# selfbus_dap_debugger.net
KiCad netlist of a schematic drawn in EAGLE
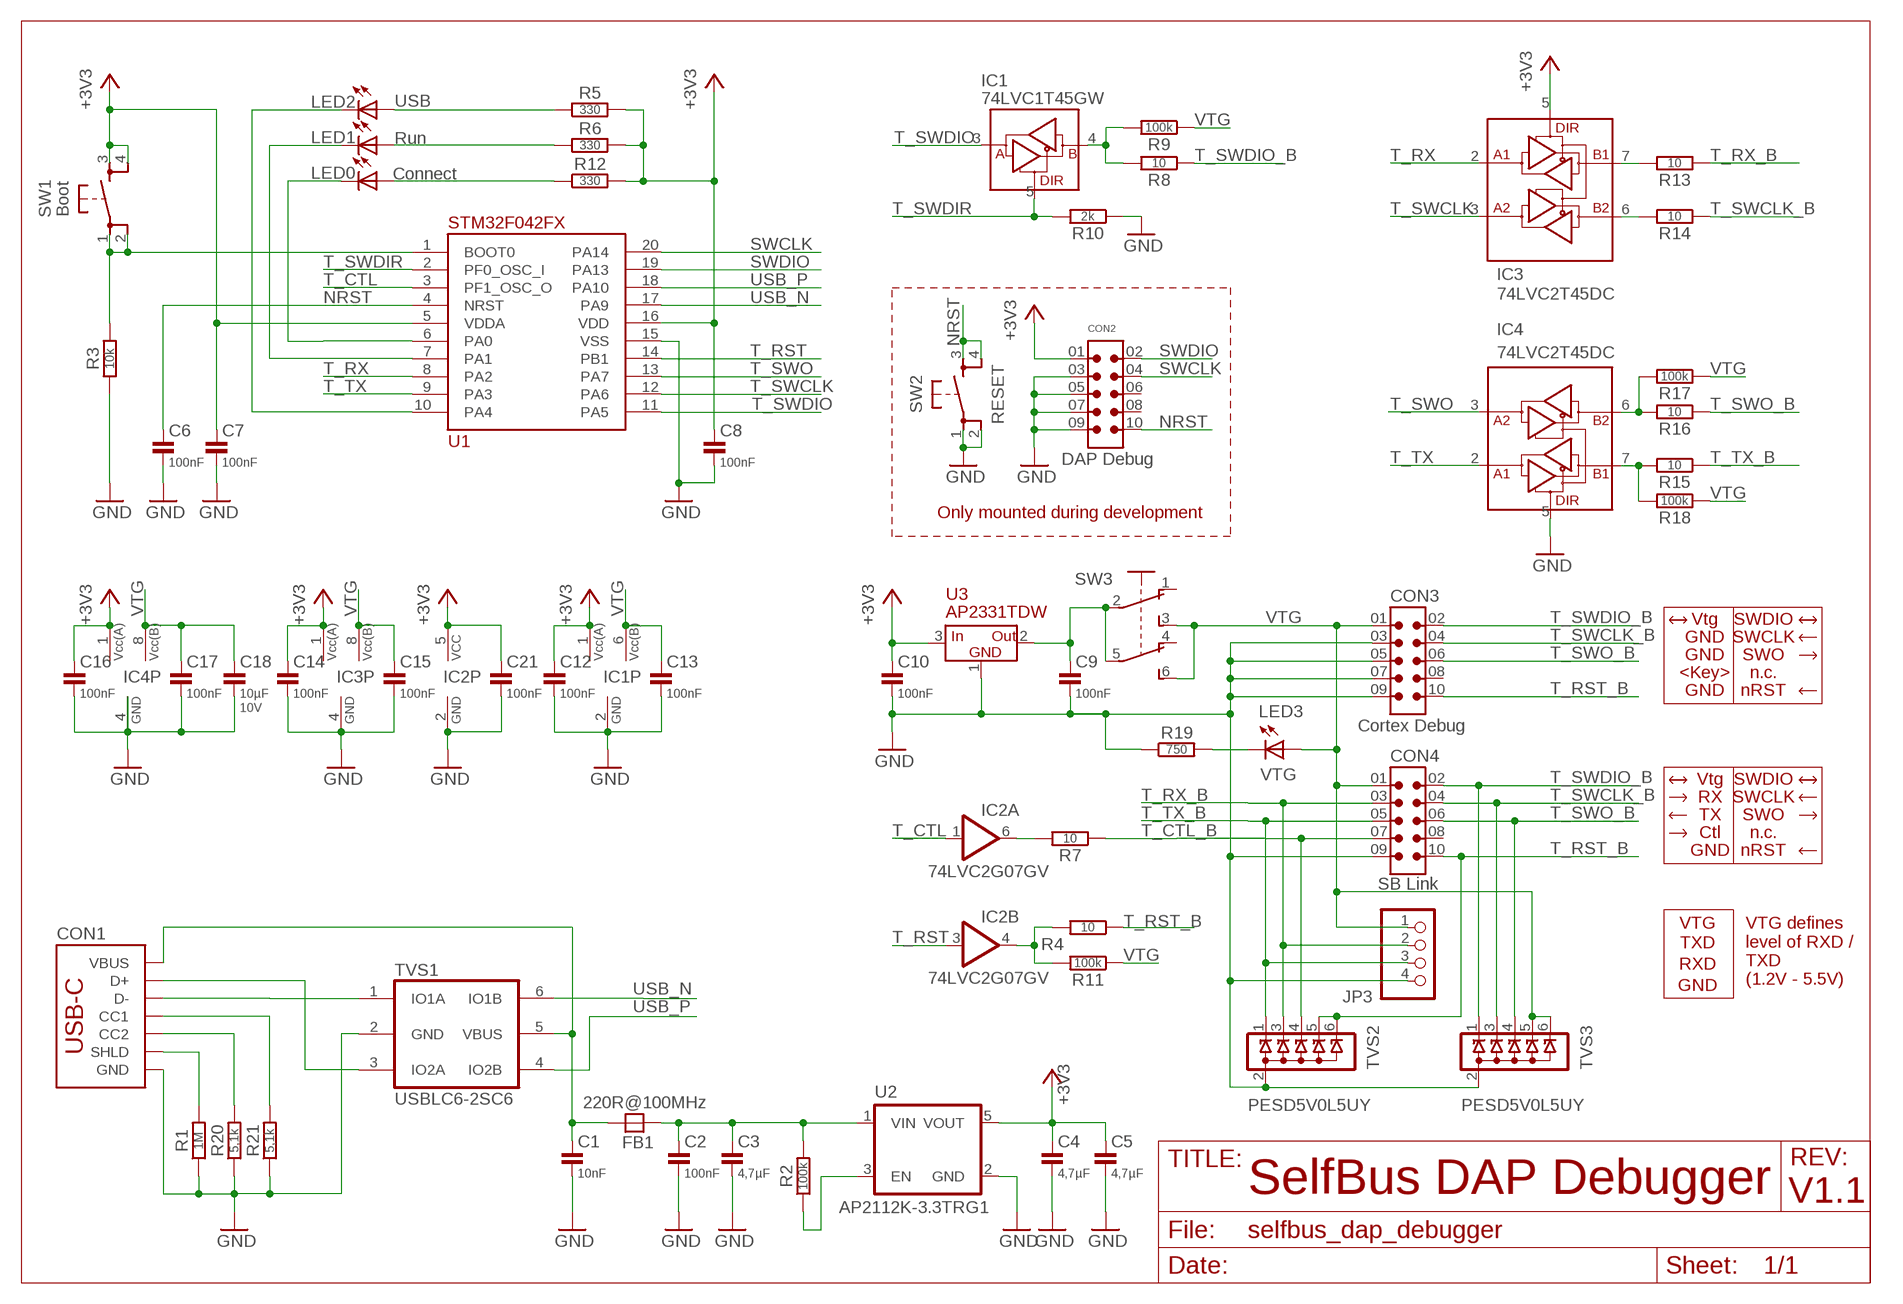
[diagram p0: schematic, sheet 1]

(export (version "E")
  (design (tool "Eeschema 10.0.6"))
  (components
    (comp (ref "C1")
      (value "10nF")
      (footprint "eagle-import:C0805")
      (libsource (lib "eagle-import") (part "C-EUC0805"))
    )
    (comp (ref "C2")
      (value "100nF")
      (footprint "eagle-import:C0805")
      (libsource (lib "eagle-import") (part "C-EUC0805"))
    )
    (comp (ref "C3")
      (value "4,7µF")
      (footprint "eagle-import:C0805")
      (libsource (lib "eagle-import") (part "C-EUC0805"))
    )
    (comp (ref "C4")
      (value "4,7µF")
      (footprint "eagle-import:C0805")
      (libsource (lib "eagle-import") (part "C-EUC0805"))
    )
    (comp (ref "C5")
      (value "4,7µF")
      (footprint "eagle-import:C0805")
      (libsource (lib "eagle-import") (part "C-EUC0805"))
    )
    (comp (ref "C6")
      (value "100nF")
      (footprint "eagle-import:C0805")
      (libsource (lib "eagle-import") (part "C-EUC0805"))
    )
    (comp (ref "C7")
      (value "100nF")
      (footprint "eagle-import:C0805")
      (libsource (lib "eagle-import") (part "C-EUC0805"))
    )
    (comp (ref "C8")
      (value "100nF")
      (footprint "eagle-import:C0805")
      (libsource (lib "eagle-import") (part "C-EUC0805"))
    )
    (comp (ref "C9")
      (value "100nF")
      (footprint "eagle-import:C0805")
      (libsource (lib "eagle-import") (part "C-EUC0805"))
    )
    (comp (ref "C10")
      (value "100nF")
      (footprint "eagle-import:C0805")
      (libsource (lib "eagle-import") (part "C-EUC0805"))
    )
    (comp (ref "C12")
      (value "100nF")
      (footprint "eagle-import:C0805")
      (libsource (lib "eagle-import") (part "C-EUC0805"))
    )
    (comp (ref "C13")
      (value "100nF")
      (footprint "eagle-import:C0805")
      (libsource (lib "eagle-import") (part "C-EUC0805"))
    )
    (comp (ref "C14")
      (value "100nF")
      (footprint "eagle-import:C0805")
      (libsource (lib "eagle-import") (part "C-EUC0805"))
    )
    (comp (ref "C15")
      (value "100nF")
      (footprint "eagle-import:C0805")
      (libsource (lib "eagle-import") (part "C-EUC0805"))
    )
    (comp (ref "C16")
      (value "100nF")
      (footprint "eagle-import:C0805")
      (libsource (lib "eagle-import") (part "C-EUC0805"))
    )
    (comp (ref "C17")
      (value "100nF")
      (footprint "eagle-import:C0805")
      (libsource (lib "eagle-import") (part "C-EUC0805"))
    )
    (comp (ref "C18")
      (value "10µF")
      (footprint "eagle-import:C0805")
      (fields (field (name "VOLTAGE") "10V"))
      (libsource (lib "eagle-import") (part "C-EUC0805"))
    )
    (comp (ref "C21")
      (value "100nF")
      (footprint "eagle-import:C0805")
      (libsource (lib "eagle-import") (part "C-EUC0805"))
    )
    (comp (ref "CON1")
      (value "XKB U262-161N-4BVC11")
      (footprint "eagle-import:USB-C-16P-2LAYER-PADS")
      (libsource (lib "eagle-import") (part "USB_C_2-LAYER_PADS"))
    )
    (comp (ref "CON2")
      (value "SHF-105-01-X-D-TH")
      (footprint "eagle-import:SAMTEC_SHF-105-01-X-D-TH")
      (libsource (lib "eagle-import") (part "SHF-105-01-X-D-TH"))
    )
    (comp (ref "CON3")
      (value "SHF-105-01-X-D-TH")
      (footprint "eagle-import:SAMTEC_SHF-105-01-X-D-TH")
      (libsource (lib "eagle-import") (part "SHF-105-01-X-D-TH"))
    )
    (comp (ref "CON4")
      (value "SAMTEC-LTMM-105-02-T-D")
      (footprint "eagle-import:SAMTEC-LTMM-105-02-T-D")
      (libsource (lib "eagle-import") (part "SAMTEC-LTMM-105-02-T-D"))
    )
    (comp (ref "FB1")
      (value "220R@100MHz")
      (footprint "eagle-import:FB0805")
      (fields (field (name "PART#") "MPZ2012S221ATD25"))
      (libsource (lib "eagle-import") (part "FB"))
    )
    (comp (ref "IC1")
      (value "74LVC1T45GW")
      (footprint "eagle-import:SOT363")
      (fields
        (field (name "LCSC#") "C478004")
        (field (name "LCSC#2") "C548484")
        (field (name "LCSC#3") "C9382")
        (field (name "MOUSER#") "771-74LVC1T45GW125")
        (field (name "MOUSER#2") "771-74LVC1T45GWQ100H")
        (field (name "MOUSER#3") "595-74LVC1T45QDCKRQ1")
        (field (name "PART#") "74LVC1T45GW,125")
        (field (name "PART#2") "74LVC1T45GW-Q100H")
        (field (name "PART#3") "SN74LVC1T45DCKR")
        (field (name "PART_MFR") "NXP")
        (field (name "PART_MFR2") "NXP")
        (field (name "PART_MFR3") "TI")
      )
      (libsource (lib "eagle-import") (part "741T45GWLVC"))
    )
    (comp (ref "IC2")
      (value "74LVC2G07GV")
      (footprint "eagle-import:SOT23-6")
      (fields
        (field (name "LCSC#") "C548568")
        (field (name "MOUSER#") "771-LVC2G07GV125")
        (field (name "PART#") "74LVC2G07GV,125")
        (field (name "PART_MFR") "NXP")
      )
      (libsource (lib "eagle-import") (part "742G07GVLVC"))
    )
    (comp (ref "IC3")
      (value "74LVC2T45DC")
      (footprint "eagle-import:VSSOP8(0.5)")
      (fields
        (field (name "LCSC#") "C15741")
        (field (name "LCSC#2") "C139524")
        (field (name "MOUSER#") "595-SN74LVC2T45DCUT")
        (field (name "MOUSER#2") "771-74LVCH2T45DC125")
        (field (name "PART#") "SN74LVC2T45DCU")
        (field (name "PART#2") "74LVCH2T45DC,125")
        (field (name "PART_MFR") "TI")
        (field (name "PART_MFR2") "NXP")
      )
      (libsource (lib "eagle-import") (part "742T45DCLVC"))
    )
    (comp (ref "IC4")
      (value "74LVC2T45DC")
      (footprint "eagle-import:VSSOP8(0.5)")
      (libsource (lib "eagle-import") (part "742T45DCLVC"))
    )
    (comp (ref "JP3")
      (value "PINHD-1X4")
      (footprint "eagle-import:1X04")
      (libsource (lib "eagle-import") (part "PINHD-1X4"))
    )
    (comp (ref "LED0")
      (value "Connect")
      (footprint "eagle-import:LED_3MM_GREEN")
      (libsource (lib "eagle-import") (part "LED_3MM(T1)_GREEN"))
    )
    (comp (ref "LED1")
      (value "Run")
      (footprint "eagle-import:LED_3MM_YELLOW")
      (libsource (lib "eagle-import") (part "LED_3MM(T1)_YELLOW"))
    )
    (comp (ref "LED2")
      (value "USB")
      (footprint "eagle-import:LED_3MM_GREEN")
      (libsource (lib "eagle-import") (part "LED_3MM(T1)_GREEN"))
    )
    (comp (ref "LED3")
      (value "VTG")
      (footprint "eagle-import:LED_3MM_RED")
      (libsource (lib "eagle-import") (part "LED_3MM(T1)_RED"))
    )
    (comp (ref "R1")
      (value "1M")
      (footprint "eagle-import:R0805")
      (libsource (lib "eagle-import") (part "R-EU_R0805"))
    )
    (comp (ref "R2")
      (value "100k")
      (footprint "eagle-import:R0805")
      (libsource (lib "eagle-import") (part "R-EU_R0805"))
    )
    (comp (ref "R3")
      (value "10k")
      (footprint "eagle-import:R0805")
      (libsource (lib "eagle-import") (part "R-EU_R0805"))
    )
    (comp (ref "R4")
      (value "10")
      (footprint "eagle-import:R0805")
      (libsource (lib "eagle-import") (part "R-EU_R0805"))
    )
    (comp (ref "R5")
      (value "330")
      (footprint "eagle-import:R0805")
      (libsource (lib "eagle-import") (part "R-EU_R0805"))
    )
    (comp (ref "R6")
      (value "330")
      (footprint "eagle-import:R0805")
      (libsource (lib "eagle-import") (part "R-EU_R0805"))
    )
    (comp (ref "R7")
      (value "10")
      (footprint "eagle-import:R0805")
      (libsource (lib "eagle-import") (part "R-EU_R0805"))
    )
    (comp (ref "R8")
      (value "10")
      (footprint "eagle-import:R0805")
      (libsource (lib "eagle-import") (part "R-EU_R0805"))
    )
    (comp (ref "R9")
      (value "100k")
      (footprint "eagle-import:R0805")
      (libsource (lib "eagle-import") (part "R-EU_R0805"))
    )
    (comp (ref "R10")
      (value "2k")
      (footprint "eagle-import:R0805")
      (libsource (lib "eagle-import") (part "R-EU_R0805"))
    )
    (comp (ref "R11")
      (value "100k")
      (footprint "eagle-import:R0805")
      (libsource (lib "eagle-import") (part "R-EU_R0805"))
    )
    (comp (ref "R12")
      (value "330")
      (footprint "eagle-import:R0805")
      (libsource (lib "eagle-import") (part "R-EU_R0805"))
    )
    (comp (ref "R13")
      (value "10")
      (footprint "eagle-import:R0805")
      (libsource (lib "eagle-import") (part "R-EU_R0805"))
    )
    (comp (ref "R14")
      (value "10")
      (footprint "eagle-import:R0805")
      (libsource (lib "eagle-import") (part "R-EU_R0805"))
    )
    (comp (ref "R15")
      (value "10")
      (footprint "eagle-import:R0805")
      (libsource (lib "eagle-import") (part "R-EU_R0805"))
    )
    (comp (ref "R16")
      (value "10")
      (footprint "eagle-import:R0805")
      (libsource (lib "eagle-import") (part "R-EU_R0805"))
    )
    (comp (ref "R17")
      (value "100k")
      (footprint "eagle-import:R0805")
      (libsource (lib "eagle-import") (part "R-EU_R0805"))
    )
    (comp (ref "R18")
      (value "100k")
      (footprint "eagle-import:R0805")
      (libsource (lib "eagle-import") (part "R-EU_R0805"))
    )
    (comp (ref "R19")
      (value "750")
      (footprint "eagle-import:R0805")
      (libsource (lib "eagle-import") (part "R-EU_R0805"))
    )
    (comp (ref "R20")
      (value "5,1k")
      (footprint "eagle-import:R0805")
      (libsource (lib "eagle-import") (part "R-EU_R0805"))
    )
    (comp (ref "R21")
      (value "5,1k")
      (footprint "eagle-import:R0805")
      (libsource (lib "eagle-import") (part "R-EU_R0805"))
    )
    (comp (ref "SW1")
      (value "BOOT")
      (footprint "eagle-import:TACT_SWITCH_6X6_SNAP-IN_17")
      (fields (field (name "PART#") "SKHHDHA010"))
      (libsource (lib "eagle-import") (part "ALPS_SKHHDHA010"))
    )
    (comp (ref "SW2")
      (value "RESET")
      (footprint "eagle-import:TACT_SWITCH_6X6_SNAP-IN_17")
      (fields (field (name "PART#") "SKHHDHA010"))
      (libsource (lib "eagle-import") (part "ALPS_SKHHDHA010"))
    )
    (comp (ref "SW3")
      (value "XKB7070-Z")
      (footprint "eagle-import:XKB7070")
      (libsource (lib "eagle-import") (part "XKB7070-Z"))
    )
    (comp (ref "TVS1")
      (value "USBLC6-2SC6")
      (footprint "eagle-import:SOT-23-6L")
      (libsource (lib "eagle-import") (part "USBLC6-2SC6"))
    )
    (comp (ref "TVS2")
      (value "PESD5V0L5UY")
      (footprint "eagle-import:SOT363")
      (libsource (lib "eagle-import") (part "PESD5V0L5UY"))
    )
    (comp (ref "TVS3")
      (value "PESD5V0L5UY")
      (footprint "eagle-import:SOT363")
      (libsource (lib "eagle-import") (part "PESD5V0L5UY"))
    )
    (comp (ref "U1")
      (value "STM32F042FX")
      (footprint "eagle-import:TSSOP20")
      (fields (field (name "PART#") "STM32F042F4P6"))
      (libsource (lib "eagle-import") (part "STM32F042FX"))
    )
    (comp (ref "U2")
      (value "AP2112K-3.3TRG1")
      (footprint "eagle-import:SOT23-5")
      (libsource (lib "eagle-import") (part "AP2112K-3.3TRG1"))
    )
    (comp (ref "U3")
      (value "AP2331TDW")
      (footprint "eagle-import:SC59")
      (fields (field (name "PART#") "AP2331W-7"))
      (libsource (lib "eagle-import") (part "AP2331TDW"))
    )
  )
  (nets
    (net (code "1") (name "+3V3") (class "Default")
      (node (ref "C10") (pin "1") (pinfunction "1_1") (pintype "passive"))
      (node (ref "C12") (pin "1") (pinfunction "1_1") (pintype "passive"))
      (node (ref "C14") (pin "1") (pinfunction "1_1") (pintype "passive"))
      (node (ref "C16") (pin "1") (pinfunction "1_1") (pintype "passive"))
      (node (ref "C21") (pin "1") (pinfunction "1_1") (pintype "passive"))
      (node (ref "C4") (pin "1") (pinfunction "1_1") (pintype "passive"))
      (node (ref "C5") (pin "1") (pinfunction "1_1") (pintype "passive"))
      (node (ref "C7") (pin "1") (pinfunction "1_1") (pintype "passive"))
      (node (ref "C8") (pin "1") (pinfunction "1_1") (pintype "passive"))
      (node (ref "CON2") (pin "01") (pinfunction "1_01") (pintype "passive"))
      (node (ref "IC1") (pin "1") (pinfunction "VCC(A)_1") (pintype "power_in"))
      (node (ref "IC2") (pin "5") (pinfunction "VCC_5") (pintype "power_in"))
      (node (ref "IC3") (pin "1") (pinfunction "VCC(A)_1") (pintype "power_in"))
      (node (ref "IC3") (pin "5") (pinfunction "DIR_5") (pintype "input"))
      (node (ref "IC4") (pin "1") (pinfunction "VCC(A)_1") (pintype "power_in"))
      (node (ref "R12") (pin "2") (pinfunction "2_2") (pintype "passive"))
      (node (ref "R5") (pin "2") (pinfunction "2_2") (pintype "passive"))
      (node (ref "R6") (pin "2") (pinfunction "2_2") (pintype "passive"))
      (node (ref "SW1") (pin "3") (pinfunction "3_3") (pintype "passive"))
      (node (ref "SW1") (pin "4") (pinfunction "4_4") (pintype "passive"))
      (node (ref "U1") (pin "16") (pinfunction "VDD_16") (pintype "power_in"))
      (node (ref "U1") (pin "5") (pinfunction "VDDA_5") (pintype "power_in"))
      (node (ref "U2") (pin "5") (pinfunction "VOUT_5") (pintype "passive"))
      (node (ref "U3") (pin "3") (pinfunction "IN_3") (pintype "bidirectional"))
    )
    (net (code "2") (name "/NRST") (class "Default")
      (node (ref "C6") (pin "1") (pinfunction "1_1") (pintype "passive"))
      (node (ref "CON2") (pin "10") (pinfunction "10_10") (pintype "passive"))
      (node (ref "SW2") (pin "3") (pinfunction "3_3") (pintype "passive"))
      (node (ref "SW2") (pin "4") (pinfunction "4_4") (pintype "passive"))
      (node (ref "U1") (pin "4") (pinfunction "NRST_4") (pintype "input"))
    )
    (net (code "3") (name "/SWCLK") (class "Default")
      (node (ref "CON2") (pin "04") (pinfunction "4_04") (pintype "passive"))
      (node (ref "U1") (pin "20") (pinfunction "PA14_20") (pintype "bidirectional"))
    )
    (net (code "4") (name "/SWDIO") (class "Default")
      (node (ref "CON2") (pin "02") (pinfunction "2_02") (pintype "passive"))
      (node (ref "U1") (pin "19") (pinfunction "PA13_19") (pintype "bidirectional"))
    )
    (net (code "5") (name "/T_CTL") (class "Default")
      (node (ref "IC2") (pin "1") (pinfunction "IN_1") (pintype "input"))
      (node (ref "U1") (pin "3") (pinfunction "PF1_OSC_O_3") (pintype "bidirectional"))
    )
    (net (code "6") (name "/T_CTL_B") (class "Default")
      (node (ref "CON4") (pin "07") (pinfunction "7_07") (pintype "passive"))
      (node (ref "R7") (pin "1") (pinfunction "1_1") (pintype "passive"))
      (node (ref "TVS2") (pin "4") (pinfunction "C3_4") (pintype "passive"))
    )
    (net (code "7") (name "/T_RST") (class "Default")
      (node (ref "IC2") (pin "3") (pinfunction "IN_3") (pintype "input"))
      (node (ref "U1") (pin "14") (pinfunction "PB1_14") (pintype "bidirectional"))
    )
    (net (code "8") (name "/T_RST_B") (class "Default")
      (node (ref "CON3") (pin "10") (pinfunction "10_10") (pintype "passive"))
      (node (ref "CON4") (pin "10") (pinfunction "10_10") (pintype "passive"))
      (node (ref "R4") (pin "1") (pinfunction "1_1") (pintype "passive"))
      (node (ref "TVS2") (pin "5") (pinfunction "C4_5") (pintype "passive"))
      (node (ref "TVS2") (pin "6") (pinfunction "C5_6") (pintype "passive"))
    )
    (net (code "9") (name "/T_RX") (class "Default")
      (node (ref "IC3") (pin "2") (pinfunction "A1_2") (pintype "bidirectional"))
      (node (ref "U1") (pin "8") (pinfunction "PA2_8") (pintype "bidirectional"))
    )
    (net (code "10") (name "/T_RX_B") (class "Default")
      (node (ref "CON4") (pin "03") (pinfunction "3_03") (pintype "passive"))
      (node (ref "JP3") (pin "2") (pinfunction "2_2") (pintype "passive"))
      (node (ref "R13") (pin "1") (pinfunction "1_1") (pintype "passive"))
      (node (ref "TVS2") (pin "3") (pinfunction "C2_3") (pintype "passive"))
    )
    (net (code "11") (name "/T_SWCLK") (class "Default")
      (node (ref "IC3") (pin "3") (pinfunction "A2_3") (pintype "bidirectional"))
      (node (ref "U1") (pin "12") (pinfunction "PA6_12") (pintype "bidirectional"))
    )
    (net (code "12") (name "/T_SWCLK_B") (class "Default")
      (node (ref "CON3") (pin "04") (pinfunction "4_04") (pintype "passive"))
      (node (ref "CON4") (pin "04") (pinfunction "4_04") (pintype "passive"))
      (node (ref "R14") (pin "1") (pinfunction "1_1") (pintype "passive"))
      (node (ref "TVS3") (pin "3") (pinfunction "C2_3") (pintype "passive"))
    )
    (net (code "13") (name "/T_SWDIO") (class "Default")
      (node (ref "IC1") (pin "3") (pinfunction "A_3") (pintype "bidirectional"))
      (node (ref "U1") (pin "11") (pinfunction "PA5_11") (pintype "bidirectional"))
    )
    (net (code "14") (name "/T_SWDIO_B") (class "Default")
      (node (ref "CON3") (pin "02") (pinfunction "2_02") (pintype "passive"))
      (node (ref "CON4") (pin "02") (pinfunction "2_02") (pintype "passive"))
      (node (ref "R8") (pin "1") (pinfunction "1_1") (pintype "passive"))
      (node (ref "TVS3") (pin "1") (pinfunction "C1_1") (pintype "passive"))
    )
    (net (code "15") (name "/T_SWDIR") (class "Default")
      (node (ref "IC1") (pin "5") (pinfunction "DIR_5") (pintype "input"))
      (node (ref "R10") (pin "2") (pinfunction "2_2") (pintype "passive"))
      (node (ref "U1") (pin "2") (pinfunction "PF0_OSC_I_2") (pintype "bidirectional"))
    )
    (net (code "16") (name "/T_SWO") (class "Default")
      (node (ref "IC4") (pin "3") (pinfunction "A2_3") (pintype "bidirectional"))
      (node (ref "U1") (pin "13") (pinfunction "PA7_13") (pintype "bidirectional"))
    )
    (net (code "17") (name "/T_SWO_B") (class "Default")
      (node (ref "CON3") (pin "06") (pinfunction "6_06") (pintype "passive"))
      (node (ref "CON4") (pin "06") (pinfunction "6_06") (pintype "passive"))
      (node (ref "R16") (pin "1") (pinfunction "1_1") (pintype "passive"))
      (node (ref "TVS3") (pin "4") (pinfunction "C3_4") (pintype "passive"))
    )
    (net (code "18") (name "/T_TX") (class "Default")
      (node (ref "IC4") (pin "2") (pinfunction "A1_2") (pintype "bidirectional"))
      (node (ref "U1") (pin "9") (pinfunction "PA3_9") (pintype "bidirectional"))
    )
    (net (code "19") (name "/T_TX_B") (class "Default")
      (node (ref "CON4") (pin "05") (pinfunction "5_05") (pintype "passive"))
      (node (ref "JP3") (pin "3") (pinfunction "3_3") (pintype "passive"))
      (node (ref "R15") (pin "1") (pinfunction "1_1") (pintype "passive"))
      (node (ref "TVS2") (pin "1") (pinfunction "C1_1") (pintype "passive"))
    )
    (net (code "20") (name "/USB_N") (class "Default")
      (node (ref "TVS1") (pin "6") (pinfunction "IO1B_6") (pintype "bidirectional"))
      (node (ref "U1") (pin "17") (pinfunction "PA9_17") (pintype "bidirectional"))
    )
    (net (code "21") (name "/USB_P") (class "Default")
      (node (ref "TVS1") (pin "4") (pinfunction "IO2B_4") (pintype "bidirectional"))
      (node (ref "U1") (pin "18") (pinfunction "PA10_18") (pintype "bidirectional"))
    )
    (net (code "22") (name "/VTG") (class "Default")
      (node (ref "C13") (pin "1") (pinfunction "1_1") (pintype "passive"))
      (node (ref "C15") (pin "1") (pinfunction "1_1") (pintype "passive"))
      (node (ref "C17") (pin "1") (pinfunction "1_1") (pintype "passive"))
      (node (ref "C18") (pin "1") (pinfunction "1_1") (pintype "passive"))
      (node (ref "CON3") (pin "01") (pinfunction "1_01") (pintype "passive"))
      (node (ref "CON4") (pin "01") (pinfunction "1_01") (pintype "passive"))
      (node (ref "IC1") (pin "6") (pinfunction "VCC(B)_6") (pintype "power_in"))
      (node (ref "IC3") (pin "8") (pinfunction "VCC(B)_8") (pintype "power_in"))
      (node (ref "IC4") (pin "8") (pinfunction "VCC(B)_8") (pintype "power_in"))
      (node (ref "JP3") (pin "1") (pinfunction "1_1") (pintype "passive"))
      (node (ref "LED3") (pin "A") (pinfunction "A_A") (pintype "passive"))
      (node (ref "R11") (pin "1") (pinfunction "1_1") (pintype "passive"))
      (node (ref "R17") (pin "1") (pinfunction "1_1") (pintype "passive"))
      (node (ref "R18") (pin "1") (pinfunction "1_1") (pintype "passive"))
      (node (ref "R9") (pin "1") (pinfunction "1_1") (pintype "passive"))
      (node (ref "SW3") (pin "3") (pinfunction "S_3") (pintype "passive"))
      (node (ref "SW3") (pin "6") (pinfunction "S_6") (pintype "passive"))
      (node (ref "TVS3") (pin "5") (pinfunction "C4_5") (pintype "passive"))
      (node (ref "TVS3") (pin "6") (pinfunction "C5_6") (pintype "passive"))
    )
    (net (code "23") (name "GND") (class "Default")
      (node (ref "C1") (pin "2") (pinfunction "2_2") (pintype "passive"))
      (node (ref "C10") (pin "2") (pinfunction "2_2") (pintype "passive"))
      (node (ref "C12") (pin "2") (pinfunction "2_2") (pintype "passive"))
      (node (ref "C13") (pin "2") (pinfunction "2_2") (pintype "passive"))
      (node (ref "C14") (pin "2") (pinfunction "2_2") (pintype "passive"))
      (node (ref "C15") (pin "2") (pinfunction "2_2") (pintype "passive"))
      (node (ref "C16") (pin "2") (pinfunction "2_2") (pintype "passive"))
      (node (ref "C17") (pin "2") (pinfunction "2_2") (pintype "passive"))
      (node (ref "C18") (pin "2") (pinfunction "2_2") (pintype "passive"))
      (node (ref "C2") (pin "2") (pinfunction "2_2") (pintype "passive"))
      (node (ref "C21") (pin "2") (pinfunction "2_2") (pintype "passive"))
      (node (ref "C3") (pin "2") (pinfunction "2_2") (pintype "passive"))
      (node (ref "C4") (pin "2") (pinfunction "2_2") (pintype "passive"))
      (node (ref "C5") (pin "2") (pinfunction "2_2") (pintype "passive"))
      (node (ref "C6") (pin "2") (pinfunction "2_2") (pintype "passive"))
      (node (ref "C7") (pin "2") (pinfunction "2_2") (pintype "passive"))
      (node (ref "C8") (pin "2") (pinfunction "2_2") (pintype "passive"))
      (node (ref "C9") (pin "2") (pinfunction "2_2") (pintype "passive"))
      (node (ref "CON1") (pin "GND") (pinfunction "GND_GND") (pintype "bidirectional"))
      (node (ref "CON1") (pin "GND2") (pinfunction "GND_GND2") (pintype "bidirectional"))
      (node (ref "CON2") (pin "03") (pinfunction "3_03") (pintype "passive"))
      (node (ref "CON2") (pin "05") (pinfunction "5_05") (pintype "passive"))
      (node (ref "CON2") (pin "07") (pinfunction "7_07") (pintype "passive"))
      (node (ref "CON2") (pin "09") (pinfunction "9_09") (pintype "passive"))
      (node (ref "CON3") (pin "03") (pinfunction "3_03") (pintype "passive"))
      (node (ref "CON3") (pin "05") (pinfunction "5_05") (pintype "passive"))
      (node (ref "CON3") (pin "07") (pinfunction "7_07") (pintype "passive"))
      (node (ref "CON3") (pin "09") (pinfunction "9_09") (pintype "passive"))
      (node (ref "CON4") (pin "09") (pinfunction "9_09") (pintype "passive"))
      (node (ref "IC1") (pin "2") (pinfunction "GND_2") (pintype "power_in"))
      (node (ref "IC2") (pin "2") (pinfunction "GND_2") (pintype "power_in"))
      (node (ref "IC3") (pin "4") (pinfunction "GND_4") (pintype "power_in"))
      (node (ref "IC4") (pin "4") (pinfunction "GND_4") (pintype "power_in"))
      (node (ref "IC4") (pin "5") (pinfunction "DIR_5") (pintype "input"))
      (node (ref "JP3") (pin "4") (pinfunction "4_4") (pintype "passive"))
      (node (ref "R1") (pin "1") (pinfunction "1_1") (pintype "passive"))
      (node (ref "R10") (pin "1") (pinfunction "1_1") (pintype "passive"))
      (node (ref "R19") (pin "1") (pinfunction "1_1") (pintype "passive"))
      (node (ref "R20") (pin "1") (pinfunction "1_1") (pintype "passive"))
      (node (ref "R21") (pin "1") (pinfunction "1_1") (pintype "passive"))
      (node (ref "R3") (pin "1") (pinfunction "1_1") (pintype "passive"))
      (node (ref "SW2") (pin "1") (pinfunction "1_1") (pintype "passive"))
      (node (ref "SW2") (pin "2") (pinfunction "2_2") (pintype "passive"))
      (node (ref "TVS1") (pin "2") (pinfunction "GND_2") (pintype "bidirectional"))
      (node (ref "TVS2") (pin "2") (pinfunction "A_2") (pintype "passive"))
      (node (ref "TVS3") (pin "2") (pinfunction "A_2") (pintype "passive"))
      (node (ref "U1") (pin "15") (pinfunction "VSS_15") (pintype "power_in"))
      (node (ref "U2") (pin "2") (pinfunction "GND_2") (pintype "input"))
      (node (ref "U3") (pin "1") (pinfunction "GND_1") (pintype "bidirectional"))
    )
    (net (code "24") (name "Net-(CON1-CC1)") (class "Default")
      (node (ref "CON1") (pin "A5") (pinfunction "CC1_A5") (pintype "bidirectional"))
      (node (ref "R21") (pin "2") (pinfunction "2_2") (pintype "passive"))
    )
    (net (code "25") (name "Net-(CON1-CC2)") (class "Default")
      (node (ref "CON1") (pin "B5") (pinfunction "CC2_B5") (pintype "bidirectional"))
      (node (ref "R20") (pin "2") (pinfunction "2_2") (pintype "passive"))
    )
    (net (code "26") (name "Net-(CON1-SHLD-PadSHLD1)") (class "Default")
      (node (ref "CON1") (pin "SHLD1") (pinfunction "SHLD_SHLD1") (pintype "bidirectional"))
      (node (ref "CON1") (pin "SHLD2") (pinfunction "SHLD_SHLD2") (pintype "bidirectional"))
      (node (ref "CON1") (pin "SHLD3") (pinfunction "SHLD_SHLD3") (pintype "bidirectional"))
      (node (ref "CON1") (pin "SHLD4") (pinfunction "SHLD_SHLD4") (pintype "bidirectional"))
      (node (ref "R1") (pin "2") (pinfunction "2_2") (pintype "passive"))
    )
    (net (code "27") (name "Net-(IC1A-B)") (class "Default")
      (node (ref "IC1") (pin "4") (pinfunction "B_4") (pintype "tri_state"))
      (node (ref "R8") (pin "2") (pinfunction "2_2") (pintype "passive"))
      (node (ref "R9") (pin "2") (pinfunction "2_2") (pintype "passive"))
    )
    (net (code "28") (name "Net-(IC2A-OUT)") (class "Default")
      (node (ref "IC2") (pin "6") (pinfunction "OUT_6") (pintype "open_collector"))
      (node (ref "R7") (pin "2") (pinfunction "2_2") (pintype "passive"))
    )
    (net (code "29") (name "Net-(IC2B-OUT)") (class "Default")
      (node (ref "IC2") (pin "4") (pinfunction "OUT_4") (pintype "open_collector"))
      (node (ref "R11") (pin "2") (pinfunction "2_2") (pintype "passive"))
      (node (ref "R4") (pin "2") (pinfunction "2_2") (pintype "passive"))
    )
    (net (code "30") (name "Net-(IC3A-B1)") (class "Default")
      (node (ref "IC3") (pin "7") (pinfunction "B1_7") (pintype "tri_state"))
      (node (ref "R13") (pin "2") (pinfunction "2_2") (pintype "passive"))
    )
    (net (code "31") (name "Net-(IC3A-B2)") (class "Default")
      (node (ref "IC3") (pin "6") (pinfunction "B2_6") (pintype "tri_state"))
      (node (ref "R14") (pin "2") (pinfunction "2_2") (pintype "passive"))
    )
    (net (code "32") (name "Net-(IC4A-B1)") (class "Default")
      (node (ref "IC4") (pin "7") (pinfunction "B1_7") (pintype "tri_state"))
      (node (ref "R15") (pin "2") (pinfunction "2_2") (pintype "passive"))
      (node (ref "R18") (pin "2") (pinfunction "2_2") (pintype "passive"))
    )
    (net (code "33") (name "Net-(IC4A-B2)") (class "Default")
      (node (ref "IC4") (pin "6") (pinfunction "B2_6") (pintype "tri_state"))
      (node (ref "R16") (pin "2") (pinfunction "2_2") (pintype "passive"))
      (node (ref "R17") (pin "2") (pinfunction "2_2") (pintype "passive"))
    )
    (net (code "34") (name "Net-(LED0-PadA)") (class "Default")
      (node (ref "LED0") (pin "A") (pinfunction "A_A") (pintype "passive"))
      (node (ref "R12") (pin "1") (pinfunction "1_1") (pintype "passive"))
    )
    (net (code "35") (name "Net-(LED1-PadA)") (class "Default")
      (node (ref "LED1") (pin "A") (pinfunction "A_A") (pintype "passive"))
      (node (ref "R6") (pin "1") (pinfunction "1_1") (pintype "passive"))
    )
    (net (code "36") (name "Net-(LED2-PadA)") (class "Default")
      (node (ref "LED2") (pin "A") (pinfunction "A_A") (pintype "passive"))
      (node (ref "R5") (pin "1") (pinfunction "1_1") (pintype "passive"))
    )
    (net (code "37") (name "Net-(LED3-PadC)") (class "Default")
      (node (ref "LED3") (pin "C") (pinfunction "C_C") (pintype "passive"))
      (node (ref "R19") (pin "2") (pinfunction "2_2") (pintype "passive"))
    )
    (net (code "38") (name "Net-(SW3A-P)") (class "Default")
      (node (ref "C9") (pin "1") (pinfunction "1_1") (pintype "passive"))
      (node (ref "SW3") (pin "2") (pinfunction "P_2") (pintype "passive"))
      (node (ref "SW3") (pin "5") (pinfunction "P_5") (pintype "passive"))
      (node (ref "U3") (pin "2") (pinfunction "OUT_2") (pintype "bidirectional"))
    )
    (net (code "39") (name "Net-(TVS1-IO1A)") (class "Default")
      (node (ref "CON1") (pin "A7") (pinfunction "D-_A7") (pintype "bidirectional"))
      (node (ref "CON1") (pin "B7") (pinfunction "D-_B7") (pintype "bidirectional"))
      (node (ref "TVS1") (pin "1") (pinfunction "IO1A_1") (pintype "bidirectional"))
    )
    (net (code "40") (name "Net-(TVS1-IO2A)") (class "Default")
      (node (ref "CON1") (pin "A6") (pinfunction "D+_A6") (pintype "bidirectional"))
      (node (ref "CON1") (pin "B6") (pinfunction "D+_B6") (pintype "bidirectional"))
      (node (ref "TVS1") (pin "3") (pinfunction "IO2A_3") (pintype "bidirectional"))
    )
    (net (code "41") (name "Net-(TVS1-VBUS)") (class "Default")
      (node (ref "C1") (pin "1") (pinfunction "1_1") (pintype "passive"))
      (node (ref "CON1") (pin "VBUS1") (pinfunction "VBUS_VBUS1") (pintype "bidirectional"))
      (node (ref "CON1") (pin "VBUS2") (pinfunction "VBUS_VBUS2") (pintype "bidirectional"))
      (node (ref "FB1") (pin "1") (pinfunction "1_1") (pintype "passive"))
      (node (ref "TVS1") (pin "5") (pinfunction "VBUS_5") (pintype "bidirectional"))
    )
    (net (code "42") (name "Net-(U1-BOOT0)") (class "Default")
      (node (ref "R3") (pin "2") (pinfunction "2_2") (pintype "passive"))
      (node (ref "SW1") (pin "1") (pinfunction "1_1") (pintype "passive"))
      (node (ref "SW1") (pin "2") (pinfunction "2_2") (pintype "passive"))
      (node (ref "U1") (pin "1") (pinfunction "BOOT0_1") (pintype "bidirectional"))
    )
    (net (code "43") (name "Net-(U1-PA0)") (class "Default")
      (node (ref "LED0") (pin "C") (pinfunction "C_C") (pintype "passive"))
      (node (ref "U1") (pin "6") (pinfunction "PA0_6") (pintype "bidirectional"))
    )
    (net (code "44") (name "Net-(U1-PA1)") (class "Default")
      (node (ref "LED1") (pin "C") (pinfunction "C_C") (pintype "passive"))
      (node (ref "U1") (pin "7") (pinfunction "PA1_7") (pintype "bidirectional"))
    )
    (net (code "45") (name "Net-(U1-PA4)") (class "Default")
      (node (ref "LED2") (pin "C") (pinfunction "C_C") (pintype "passive"))
      (node (ref "U1") (pin "10") (pinfunction "PA4_10") (pintype "bidirectional"))
    )
    (net (code "46") (name "Net-(U2-EN)") (class "Default")
      (node (ref "R2") (pin "1") (pinfunction "1_1") (pintype "passive"))
      (node (ref "U2") (pin "3") (pinfunction "EN_3") (pintype "input"))
    )
    (net (code "47") (name "Net-(U2-VIN)") (class "Default")
      (node (ref "C2") (pin "1") (pinfunction "1_1") (pintype "passive"))
      (node (ref "C3") (pin "1") (pinfunction "1_1") (pintype "passive"))
      (node (ref "FB1") (pin "2") (pinfunction "2_2") (pintype "passive"))
      (node (ref "R2") (pin "2") (pinfunction "2_2") (pintype "passive"))
      (node (ref "U2") (pin "1") (pinfunction "VIN_1") (pintype "input"))
    )
    (net (code "48") (name "unconnected-(CON2-6-Pad06)") (class "Default")
      (node (ref "CON2") (pin "06") (pinfunction "6_06") (pintype "passive"))
    )
    (net (code "49") (name "unconnected-(CON2-8-Pad08)") (class "Default")
      (node (ref "CON2") (pin "08") (pinfunction "8_08") (pintype "passive"))
    )
    (net (code "50") (name "unconnected-(CON3-8-Pad08)") (class "Default")
      (node (ref "CON3") (pin "08") (pinfunction "8_08") (pintype "passive"))
    )
    (net (code "51") (name "unconnected-(CON4-8-Pad08)") (class "Default")
      (node (ref "CON4") (pin "08") (pinfunction "8_08") (pintype "passive"))
    )
    (net (code "52") (name "unconnected-(SW3A-O-Pad1)") (class "Default")
      (node (ref "SW3") (pin "1") (pinfunction "O_1") (pintype "passive"))
    )
    (net (code "53") (name "unconnected-(SW3B-O-Pad4)") (class "Default")
      (node (ref "SW3") (pin "4") (pinfunction "O_4") (pintype "passive"))
    )
  )
)
